# Power_management.net
KiCad netlist of a schematic drawn in Altium Designer
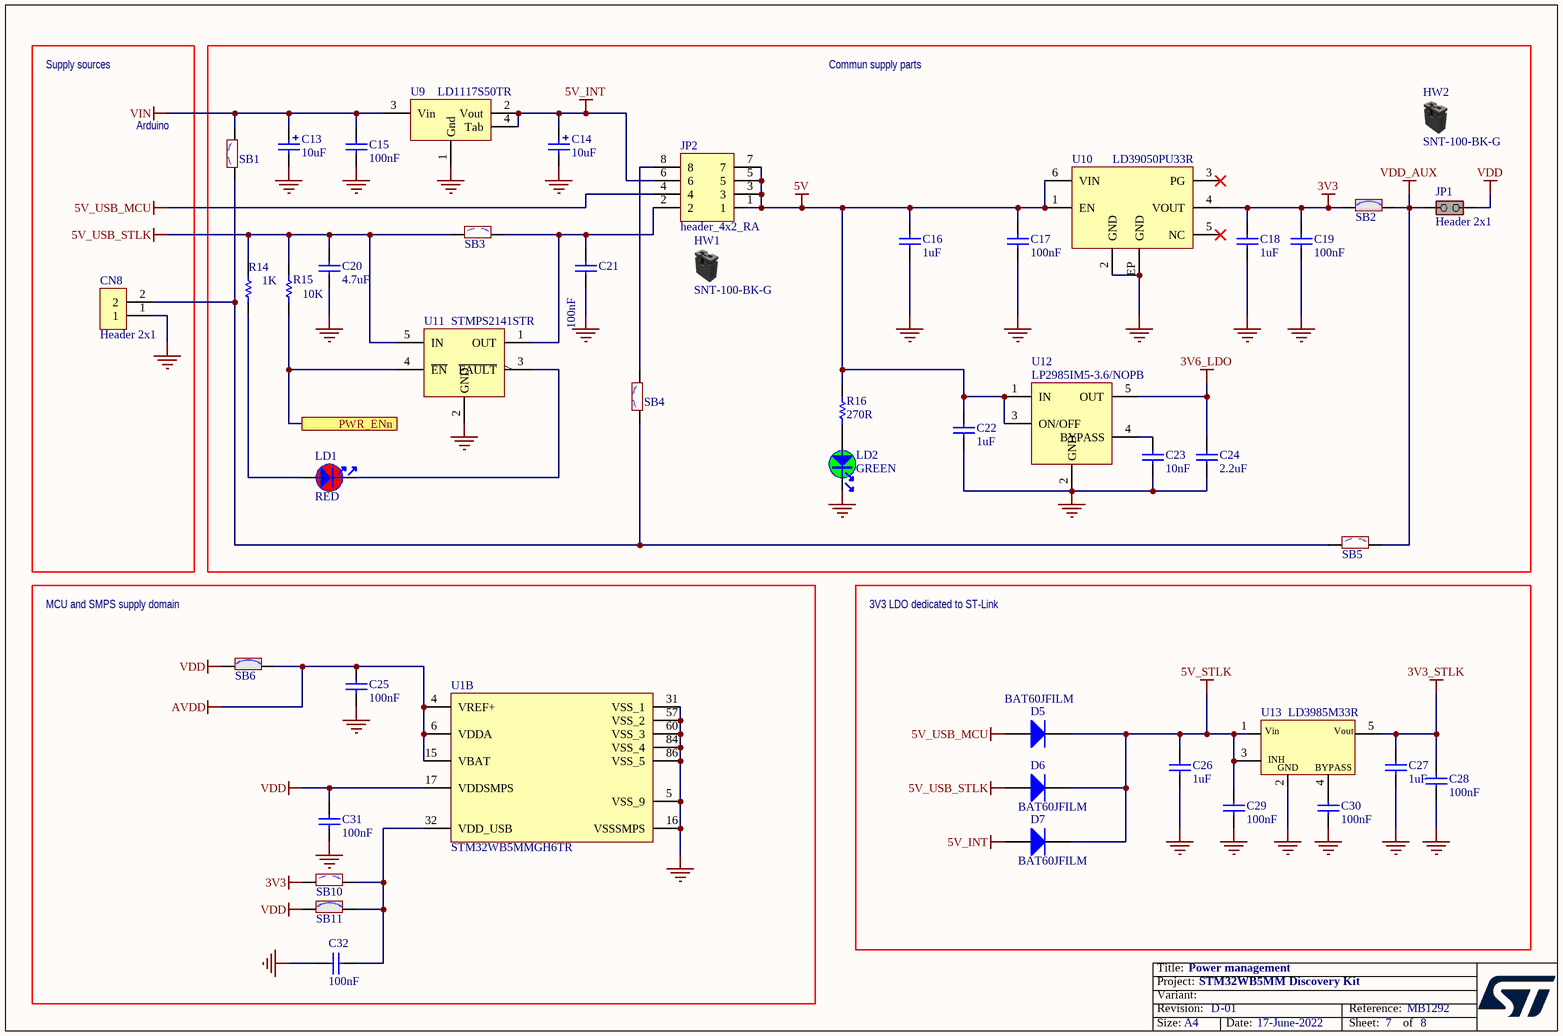
[diagram p0: Power_management.SchDoc]

(export (version "E")
  (design (tool "Eeschema 10.0.6"))
  (components
    (comp (ref "C13")
      (value "10uF")
      (footprint "CPOL_TAJ-B_1210_H210")
      (description "Capacitor, Tantalum, 10uF, 25V,2.5ohms, 10%, pkg Type_B (3528 metric), T=1.9mm")
      (fields
        (field (name "INTERNAL_PART_NUMBER") "MCD-00324")
        (field (name "MANUFACTURER_PART_NUMBER") "TAJB106K025RNJ")
      )
      (libsource (lib "MCD_PARTS_database") (part "Cap_POL_TANA"))
    )
    (comp (ref "C14")
      (value "10uF")
      (footprint "CPOL_TAJ-B_1210_H210")
      (description "Capacitor, Tantalum, 10uF, 25V,2.5ohms, 10%, pkg Type_B (3528 metric), T=1.9mm")
      (fields
        (field (name "INTERNAL_PART_NUMBER") "MCD-00324")
        (field (name "MANUFACTURER_PART_NUMBER") "TAJB106K025RNJ")
      )
      (libsource (lib "MCD_PARTS_database") (part "Cap_POL_TANA"))
    )
    (comp (ref "C15")
      (value "100nF")
      (footprint "C0805_H0P85")
      (description "Capacitor, MLCC, 100nF, 50V, X7R, 10%, 0805, T=0,85mm")
      (fields
        (field (name "INTERNAL_PART_NUMBER") "MCD-01525")
        (field (name "MANUFACTURER_PART_NUMBER") "CC0805KRX7R9BB104")
      )
      (libsource (lib "MCD_PARTS_database") (part "Capacitor"))
    )
    (comp (ref "C16")
      (value "1uF")
      (footprint "C0805_H0P85")
      (description "Capacitor, MLCC, 1uF, 16V, X5R, +/-10%, 0805, T=0.85mm")
      (fields
        (field (name "INTERNAL_PART_NUMBER") "MCD-01550")
        (field (name "MANUFACTURER_PART_NUMBER") "CC0805KRX5R7BB105")
      )
      (libsource (lib "MCD_PARTS_database") (part "Capacitor"))
    )
    (comp (ref "C17")
      (value "100nF")
      (footprint "C0201_H0P3")
      (description "Capacitor, MLCC,100nF, 10V, X7R, +/-10%, 0201, T=0.3mm")
      (fields
        (field (name "INTERNAL_PART_NUMBER") "MCD-01535")
        (field (name "MANUFACTURER_PART_NUMBER") "GRM033R61A104KE15")
      )
      (libsource (lib "MCD_PARTS_database") (part "Capacitor"))
    )
    (comp (ref "C18")
      (value "1uF")
      (footprint "C0805_H0P85")
      (description "Capacitor, MLCC, 1uF, 16V, X5R, +/-10%, 0805, T=0.85mm")
      (fields
        (field (name "INTERNAL_PART_NUMBER") "MCD-01550")
        (field (name "MANUFACTURER_PART_NUMBER") "CC0805KRX5R7BB105")
      )
      (libsource (lib "MCD_PARTS_database") (part "Capacitor"))
    )
    (comp (ref "C19")
      (value "100nF")
      (footprint "C0201_H0P3")
      (description "Capacitor, MLCC,100nF, 10V, X7R, +/-10%, 0201, T=0.3mm")
      (fields
        (field (name "INTERNAL_PART_NUMBER") "MCD-01535")
        (field (name "MANUFACTURER_PART_NUMBER") "GRM033R61A104KE15")
      )
      (libsource (lib "MCD_PARTS_database") (part "Capacitor"))
    )
    (comp (ref "C20")
      (value "4.7uF")
      (footprint "C0603_H0P8")
      (description "Capacitor, MLCC, 4.7uF, 10V, X5R, +/-10%, 0603, T=0.8mm")
      (fields
        (field (name "INTERNAL_PART_NUMBER") "MCD-01721")
        (field (name "MANUFACTURER_PART_NUMBER") "CC0603KRX5R6BB475")
      )
      (libsource (lib "MCD_PARTS_database") (part "Capacitor"))
    )
    (comp (ref "C21")
      (value "100nF")
      (footprint "C0805_H0P85")
      (description "Capacitor, MLCC, 100nF, 50V, X7R, 10%, 0805, T=0,85mm")
      (fields
        (field (name "INTERNAL_PART_NUMBER") "MCD-01525")
        (field (name "MANUFACTURER_PART_NUMBER") "CC0805KRX7R9BB104")
      )
      (libsource (lib "MCD_PARTS_database") (part "Capacitor"))
    )
    (comp (ref "C22")
      (value "1uF")
      (footprint "C0603")
      (description "Capacitor, MLCC, 1uF, 16V, X5R, +/-10%, 0603, T=0,8mm")
      (fields
        (field (name "INTERNAL_PART_NUMBER") "MCD-00010")
        (field (name "MANUFACTURER_PART_NUMBER") "CC0603KRX5R7BB105")
      )
      (libsource (lib "MCD_PARTS_database") (part "Capacitor"))
    )
    (comp (ref "C23")
      (value "10nF")
      (footprint "C0603")
      (description "Capacitor, MLCC, 10nF, 16V, X7R, +/-10%, 0603, T=0.8mm")
      (fields
        (field (name "INTERNAL_PART_NUMBER") "MCD-01007")
        (field (name "MANUFACTURER_PART_NUMBER") "CC0603KRX7R7BB103")
      )
      (libsource (lib "MCD_PARTS_database") (part "Capacitor"))
    )
    (comp (ref "C24")
      (value "2.2uF")
      (footprint "C0603")
      (description "Capacitor, MLCC, 2.2uF, 10V, X5R, +/- 10%, 0603, T=0,8mm")
      (fields
        (field (name "INTERNAL_PART_NUMBER") "MCD-00012")
        (field (name "MANUFACTURER_PART_NUMBER") "CC0603KRX5R6BB225")
      )
      (libsource (lib "MCD_PARTS_database") (part "Capacitor"))
    )
    (comp (ref "C25")
      (value "100nF")
      (footprint "C0201_H0P3")
      (description "Capacitor, MLCC,100nF, 10V, X7R, +/-10%, 0201, T=0.3mm")
      (fields
        (field (name "INTERNAL_PART_NUMBER") "MCD-01535")
        (field (name "MANUFACTURER_PART_NUMBER") "GRM033R61A104KE15")
      )
      (libsource (lib "MCD_PARTS_database") (part "Capacitor"))
    )
    (comp (ref "C26")
      (value "1uF")
      (footprint "C0402")
      (description "Capacitor, MLCC, 1uF, 10V, X5R, +/-10%, 0402, T=0.5mm")
      (fields
        (field (name "INTERNAL_PART_NUMBER") "MCD-01722")
        (field (name "MANUFACTURER_PART_NUMBER") "CC0402KRX5R6BB105")
      )
      (libsource (lib "MCD_PARTS_database") (part "Capacitor"))
    )
    (comp (ref "C27")
      (value "1uF")
      (footprint "C0402")
      (description "Capacitor, MLCC, 1uF, 10V, X5R, +/-10%, 0402, T=0.5mm")
      (fields
        (field (name "INTERNAL_PART_NUMBER") "MCD-01722")
        (field (name "MANUFACTURER_PART_NUMBER") "CC0402KRX5R6BB105")
      )
      (libsource (lib "MCD_PARTS_database") (part "Capacitor"))
    )
    (comp (ref "C28")
      (value "100nF")
      (footprint "C0201_H0P3")
      (description "Capacitor, MLCC,100nF, 10V, X7R, +/-10%, 0201, T=0.3mm")
      (fields
        (field (name "INTERNAL_PART_NUMBER") "MCD-01535")
        (field (name "MANUFACTURER_PART_NUMBER") "GRM033R61A104KE15")
      )
      (libsource (lib "MCD_PARTS_database") (part "Capacitor"))
    )
    (comp (ref "C29")
      (value "100nF")
      (footprint "C0201_H0P3")
      (description "Capacitor, MLCC,100nF, 10V, X7R, +/-10%, 0201, T=0.3mm")
      (fields
        (field (name "INTERNAL_PART_NUMBER") "MCD-01535")
        (field (name "MANUFACTURER_PART_NUMBER") "GRM033R61A104KE15")
      )
      (libsource (lib "MCD_PARTS_database") (part "Capacitor"))
    )
    (comp (ref "C30")
      (value "100nF")
      (footprint "C0201_H0P3")
      (description "Capacitor, MLCC,100nF, 10V, X7R, +/-10%, 0201, T=0.3mm")
      (fields
        (field (name "INTERNAL_PART_NUMBER") "MCD-01535")
        (field (name "MANUFACTURER_PART_NUMBER") "GRM033R61A104KE15")
      )
      (libsource (lib "MCD_PARTS_database") (part "Capacitor"))
    )
    (comp (ref "C31")
      (value "100nF")
      (footprint "C0201_H0P3")
      (description "Capacitor, MLCC,100nF, 10V, X7R, +/-10%, 0201, T=0.3mm")
      (fields
        (field (name "INTERNAL_PART_NUMBER") "MCD-01535")
        (field (name "MANUFACTURER_PART_NUMBER") "GRM033R61A104KE15")
      )
      (libsource (lib "MCD_PARTS_database") (part "Capacitor"))
    )
    (comp (ref "C32")
      (value "100nF")
      (footprint "C0201_H0P3")
      (description "Capacitor, MLCC,100nF, 10V, X7R, +/-10%, 0201, T=0.3mm")
      (fields
        (field (name "INTERNAL_PART_NUMBER") "MCD-01535")
        (field (name "MANUFACTURER_PART_NUMBER") "GRM033R61A104KE15")
      )
      (libsource (lib "MCD_PARTS_database") (part "Capacitor"))
    )
    (comp (ref "CN8")
      (value "Header 2x1")
      (footprint "CON_LYCONN_313102S141346")
      (description "Header 2x1, 2.54mm, VR, TH, height 5.84mm/5.08 mm, height total 13.46 mm")
      (fields
        (field (name "INTERNAL_PART_NUMBER") "MCD-01668")
        (field (name "MANUFACTURER_PART_NUMBER") "313102S141346")
      )
      (libsource (lib "MCD_PARTS_database") (part "Header 2x1"))
    )
    (comp (ref "D5")
      (value "BAT60JFILM")
      (footprint "DIO_SOD323")
      (fields
        (field (name "INTERNAL_PART_NUMBER") "MCD-00034")
        (field (name "MANUFACTURER") "STMICROELECTRONICS")
        (field (name "BMS_PART_NUMBER") "9151097")
      )
      (libsource (lib "MCD_PARTS_database") (part "BAT60JFILM"))
    )
    (comp (ref "D6")
      (value "BAT60JFILM")
      (footprint "DIO_SOD323")
      (fields
        (field (name "INTERNAL_PART_NUMBER") "MCD-00034")
        (field (name "MANUFACTURER") "STMICROELECTRONICS")
        (field (name "BMS_PART_NUMBER") "9151097")
      )
      (libsource (lib "MCD_PARTS_database") (part "BAT60JFILM"))
    )
    (comp (ref "D7")
      (value "BAT60JFILM")
      (footprint "DIO_SOD323")
      (fields
        (field (name "INTERNAL_PART_NUMBER") "MCD-00034")
        (field (name "MANUFACTURER") "STMICROELECTRONICS")
        (field (name "BMS_PART_NUMBER") "9151097")
      )
      (libsource (lib "MCD_PARTS_database") (part "BAT60JFILM"))
    )
    (comp (ref "HW1")
      (value "SNT-100-BK-G")
      (description "SHUNT 2.54mm BLACK")
      (fields (field (name "INTERNAL_PART_NUMBER") "MCD-00043") (field (name "MANUFACTURER") "SAMTEC"))
      (libsource (lib "MCD_PARTS_database") (part "Shunt Black 2.54mm"))
    )
    (comp (ref "HW2")
      (value "SNT-100-BK-G")
      (description "SHUNT 2.54mm BLACK")
      (fields (field (name "INTERNAL_PART_NUMBER") "MCD-00043") (field (name "MANUFACTURER") "SAMTEC"))
      (libsource (lib "MCD_PARTS_database") (part "Shunt Black 2.54mm"))
    )
    (comp (ref "JP1")
      (value "Header 2x1")
      (footprint "CON_SAMTEC_TSW-102-07-G-S")
      (description "Header, 2x1, 2,54mm, VR, TH, Height 5.84mm/2.54mm - Shunt Fitted by default")
      (fields
        (field (name "INTERNAL_PART_NUMBER") "MCD-01904")
        (field (name "MANUFACTURER_PART_NUMBER") "TSW-102-07-G-S")
      )
      (libsource (lib "MCD_PARTS_database") (part "Jumper_Header 2x1 Fitted"))
    )
    (comp (ref "JP2")
      (value "header_4x2_RA")
      (footprint "CON_SAMTEC_TSW-104-08-F-D-RA")
      (description "Header, 4x2, 2,29mm, RA, TH, height 5,84mm")
      (fields
        (field (name "INTERNAL_PART_NUMBER") "MCD-02037")
        (field (name "MANUFACTURER_PART_NUMBER") "TSW-104-08-F-D-RA")
      )
      (libsource (lib "MCD_PARTS_database") (part "Header 4x2"))
    )
    (comp (ref "LD1")
      (value "RED")
      (footprint "LED_0603_VISHAY_VLMS1300-GS08_RED_1A2K_H0P8")
      (description "LED Red, 0603 SMD, 2V Forward Voltage")
      (fields (field (name "INTERNAL_PART_NUMBER") "MCD-00587") (field (name "MANUFACTURER") "VISHAY"))
      (libsource (lib "MCD_PARTS_database") (part "LED_red"))
    )
    (comp (ref "LD2")
      (value "GREEN")
      (footprint "LED_0603_OSRAM_LG-Q396-PS-35_GREEN_1A2K_H0P4")
      (description "LED Green, 0603 SMD, Forward Voltage Typ=2V, Max=2.5V")
      (fields
        (field (name "INTERNAL_PART_NUMBER") "MCD-00588")
        (field (name "MANUFACTURER_PART_NUMBER") "LG Q396-PS-35")
      )
      (libsource (lib "MCD_PARTS_database") (part "LED_green"))
    )
    (comp (ref "R14")
      (value "1K")
      (footprint "R0603")
      (description "Resistor,1K,0603,1%,1/10W")
      (fields
        (field (name "INTERNAL_PART_NUMBER") "MCD-00070")
        (field (name "MANUFACTURER_PART_NUMBER") "RC0603FR-071KL")
      )
      (libsource (lib "MCD_PARTS_database") (part "Resistor"))
    )
    (comp (ref "R15")
      (value "10K")
      (footprint "R0603")
      (description "Resistor,10K,0603,1%,1/10W")
      (fields
        (field (name "INTERNAL_PART_NUMBER") "MCD-00220")
        (field (name "MANUFACTURER_PART_NUMBER") "RC0603FR-0710KL")
      )
      (libsource (lib "MCD_PARTS_database") (part "Resistor"))
    )
    (comp (ref "R16")
      (value "270R")
      (footprint "R0603")
      (description "Resistor,270R,0603,1%,1/10W")
      (fields
        (field (name "INTERNAL_PART_NUMBER") "MCD-00442")
        (field (name "MANUFACTURER_PART_NUMBER") "RC0603FR-07270RL")
      )
      (libsource (lib "MCD_PARTS_database") (part "Resistor"))
    )
    (comp (ref "SB1")
      (value "SB_OFF")
      (footprint "SOLDER-BRIDGE_R0603-0R")
      (description "Solder Bridge OFF")
      (fields
        (field (name "INTERNAL_PART_NUMBER") "MCD-00072")
        (field (name "MANUFACTURER_PART_NUMBER") "RC0603JR-070RL")
      )
      (libsource (lib "") (part "SB_OFF_1"))
    )
    (comp (ref "SB2")
      (value "SB_ON")
      (footprint "SOLDER-BRIDGE_R0603-0R")
      (description "Solder Bridge ON")
      (fields
        (field (name "INTERNAL_PART_NUMBER") "MCD-00071")
        (field (name "MANUFACTURER_PART_NUMBER") "RC0603JR-070RL")
      )
      (libsource (lib "MCD_PARTS_database") (part "SB_ON"))
    )
    (comp (ref "SB3")
      (value "SB_OFF")
      (footprint "SOLDER-BRIDGE_R0603-0R")
      (description "Solder Bridge OFF")
      (fields
        (field (name "INTERNAL_PART_NUMBER") "MCD-00072")
        (field (name "MANUFACTURER_PART_NUMBER") "RC0603JR-070RL")
      )
      (libsource (lib "MCD_PARTS_database") (part "SB_OFF"))
    )
    (comp (ref "SB4")
      (value "SB_OFF")
      (footprint "SOLDER-BRIDGE_R0603-0R")
      (description "Solder Bridge OFF")
      (fields
        (field (name "INTERNAL_PART_NUMBER") "MCD-00072")
        (field (name "MANUFACTURER_PART_NUMBER") "RC0603JR-070RL")
      )
      (libsource (lib "") (part "SB_OFF_1"))
    )
    (comp (ref "SB5")
      (value "SB_OFF")
      (footprint "SOLDER-BRIDGE_R0603-0R")
      (description "Solder Bridge OFF")
      (fields
        (field (name "INTERNAL_PART_NUMBER") "MCD-00072")
        (field (name "MANUFACTURER_PART_NUMBER") "RC0603JR-070RL")
      )
      (libsource (lib "MCD_PARTS_database") (part "SB_OFF"))
    )
    (comp (ref "SB6")
      (value "SB_ON")
      (footprint "SOLDER-BRIDGE_R0603-0R")
      (description "Solder Bridge ON")
      (fields
        (field (name "INTERNAL_PART_NUMBER") "MCD-00071")
        (field (name "MANUFACTURER_PART_NUMBER") "RC0603JR-070RL")
      )
      (libsource (lib "MCD_PARTS_database") (part "SB_ON"))
    )
    (comp (ref "SB10")
      (value "SB_OFF")
      (footprint "SOLDER-BRIDGE_R0603-0R")
      (description "Solder Bridge OFF")
      (fields
        (field (name "INTERNAL_PART_NUMBER") "MCD-00072")
        (field (name "MANUFACTURER_PART_NUMBER") "RC0603JR-070RL")
      )
      (libsource (lib "MCD_PARTS_database") (part "SB_OFF"))
    )
    (comp (ref "SB11")
      (value "SB_ON")
      (footprint "SOLDER-BRIDGE_R0603-0R")
      (description "Solder Bridge ON")
      (fields
        (field (name "INTERNAL_PART_NUMBER") "MCD-00071")
        (field (name "MANUFACTURER_PART_NUMBER") "RC0603JR-070RL")
      )
      (libsource (lib "MCD_PARTS_database") (part "SB_ON"))
    )
    (comp (ref "U1")
      (value "STM32WB5MMGH6TR")
      (footprint "MOD_DORY_STM_86P_7P3X11_H1P342")
      (description "STM32 BLE module based on STM32WB55")
      (fields
        (field (name "INTERNAL_PART_NUMBER") "MCD-01965")
        (field (name "MANUFACTURER") "STMICROELECTRONICS")
      )
      (libsource (lib "MCD_PARTS_database") (part "STM32WB5MMGH6TR"))
    )
    (comp (ref "U9")
      (value "LD1117S50TR")
      (footprint "REG_SOT223-TAB")
      (description "IC REG LDO 5V 0.8A SOT223")
      (fields
        (field (name "INTERNAL_PART_NUMBER") "MCD-00088")
        (field (name "MANUFACTURER") "STMICROELECTRONICS")
      )
      (libsource (lib "MCD_PARTS_database") (part "LD1117S50TR"))
    )
    (comp (ref "U10")
      (value "LD39050PU33R")
      (footprint "ICC_DFN6-EPAD_3X3_P095")
      (description "Low quiescent current and low noise voltage regulators")
      (fields
        (field (name "INTERNAL_PART_NUMBER") "MCD-00215")
        (field (name "MANUFACTURER") "STMICROELECTRONICS")
      )
      (libsource (lib "MCD_PARTS_database") (part "LD39050PU33R"))
    )
    (comp (ref "U11")
      (value "STMPS2141STR")
      (footprint "MOS_SOT23-5L")
      (description "Enhanced single channel power switches with active low enable pin")
      (fields
        (field (name "INTERNAL_PART_NUMBER") "MCD-00083")
        (field (name "MANUFACTURER") "STMICROELECTRONICS")
      )
      (libsource (lib "MCD_PARTS_database") (part "STMPS2141STR"))
    )
    (comp (ref "U12")
      (value "LP2985IM5-3.6/NOPB")
      (footprint "REG_SOT23-5L")
      (description "LDO VOLTAGE REGULATOR, 3.6V, 150mA, 5-SOT-23, FULL REEL")
      (fields
        (field (name "INTERNAL_PART_NUMBER") "MCD-01030")
        (field (name "MANUFACTURER") "TEXAS INSTRUMENTS")
      )
      (libsource (lib "MCD_PARTS_database") (part "LP2985IM5-3.6/NOPB"))
    )
    (comp (ref "U13")
      (value "LD3985M33R")
      (footprint "REG_SOT23-5L")
      (description "Ultra low drop-low noise BiCMOS voltage, regulators low ESR capacitors compatible")
      (fields
        (field (name "INTERNAL_PART_NUMBER") "MCD-00086")
        (field (name "MANUFACTURER") "STMICROELECTRONICS")
      )
      (libsource (lib "MCD_PARTS_database") (part "LD3985M33R"))
    )
  )
  (nets
    (net (code "1") (name "/PWR_ENn") (class "Default")
      (node (ref "R15") (pin "1") (pinfunction "1_1") (pintype "passive"))
      (node (ref "U11") (pin "4") (pinfunction "~{EN}_4") (pintype "passive"))
    )
    (net (code "2") (name "3V3") (class "Default")
      (node (ref "C18") (pin "2") (pinfunction "2_2") (pintype "passive"))
      (node (ref "C19") (pin "2") (pinfunction "2_2") (pintype "passive"))
      (node (ref "SB10") (pin "1") (pinfunction "1_1") (pintype "passive"))
      (node (ref "SB2") (pin "1") (pinfunction "1_1") (pintype "passive"))
      (node (ref "U10") (pin "4") (pinfunction "VOUT_4") (pintype "passive"))
    )
    (net (code "3") (name "3V3_STLK") (class "Default")
      (node (ref "C27") (pin "2") (pinfunction "2_2") (pintype "passive"))
      (node (ref "C28") (pin "2") (pinfunction "2_2") (pintype "passive"))
      (node (ref "U13") (pin "5") (pinfunction "Vout_5") (pintype "passive"))
    )
    (net (code "4") (name "3V6_LDO") (class "Default")
      (node (ref "C24") (pin "2") (pinfunction "2_2") (pintype "passive"))
      (node (ref "U12") (pin "5") (pinfunction "OUT_5") (pintype "passive"))
    )
    (net (code "5") (name "5V") (class "Default")
      (node (ref "C16") (pin "2") (pinfunction "2_2") (pintype "passive"))
      (node (ref "C17") (pin "2") (pinfunction "2_2") (pintype "passive"))
      (node (ref "C22") (pin "1") (pinfunction "1_1") (pintype "passive"))
      (node (ref "JP2") (pin "1") (pinfunction "1_1") (pintype "passive"))
      (node (ref "JP2") (pin "3") (pinfunction "3_3") (pintype "passive"))
      (node (ref "JP2") (pin "5") (pinfunction "5_5") (pintype "passive"))
      (node (ref "JP2") (pin "7") (pinfunction "7_7") (pintype "passive"))
      (node (ref "R16") (pin "2") (pinfunction "2_2") (pintype "passive"))
      (node (ref "U10") (pin "1") (pinfunction "EN_1") (pintype "passive"))
      (node (ref "U10") (pin "6") (pinfunction "VIN_6") (pintype "passive"))
      (node (ref "U12") (pin "1") (pinfunction "IN_1") (pintype "passive"))
      (node (ref "U12") (pin "3") (pinfunction "ON/OFF_3") (pintype "passive"))
    )
    (net (code "6") (name "5V_INT") (class "Default")
      (node (ref "C14") (pin "1") (pinfunction "1_1") (pintype "passive"))
      (node (ref "D7") (pin "1") (pinfunction "A_1") (pintype "passive"))
      (node (ref "JP2") (pin "6") (pinfunction "6_6") (pintype "passive"))
      (node (ref "U9") (pin "2") (pinfunction "Vout_2") (pintype "passive"))
      (node (ref "U9") (pin "4") (pinfunction "Tab_4") (pintype "passive"))
    )
    (net (code "7") (name "5V_STLK") (class "Default")
      (node (ref "C26") (pin "2") (pinfunction "2_2") (pintype "passive"))
      (node (ref "C29") (pin "2") (pinfunction "2_2") (pintype "passive"))
      (node (ref "D5") (pin "2") (pinfunction "K_2") (pintype "passive"))
      (node (ref "D6") (pin "2") (pinfunction "K_2") (pintype "passive"))
      (node (ref "D7") (pin "2") (pinfunction "K_2") (pintype "passive"))
      (node (ref "U13") (pin "1") (pinfunction "Vin_1") (pintype "passive"))
      (node (ref "U13") (pin "3") (pinfunction "CE_3") (pintype "passive"))
    )
    (net (code "8") (name "5V_USB_MCU") (class "Default")
      (node (ref "D5") (pin "1") (pinfunction "A_1") (pintype "passive"))
      (node (ref "JP2") (pin "4") (pinfunction "4_4") (pintype "passive"))
    )
    (net (code "9") (name "5V_USB_STLK") (class "Default")
      (node (ref "C20") (pin "2") (pinfunction "2_2") (pintype "passive"))
      (node (ref "D6") (pin "1") (pinfunction "A_1") (pintype "passive"))
      (node (ref "R14") (pin "2") (pinfunction "2_2") (pintype "passive"))
      (node (ref "R15") (pin "2") (pinfunction "2_2") (pintype "passive"))
      (node (ref "SB3") (pin "1") (pinfunction "1_1") (pintype "passive"))
      (node (ref "U11") (pin "5") (pinfunction "IN_5") (pintype "passive"))
    )
    (net (code "10") (name "AVDD") (class "Default")
      (node (ref "C25") (pin "2") (pinfunction "2_2") (pintype "passive"))
      (node (ref "SB6") (pin "2") (pinfunction "2_2") (pintype "passive"))
      (node (ref "U1") (pin "15") (pinfunction "VBAT_15") (pintype "passive"))
      (node (ref "U1") (pin "4") (pinfunction "VREF+_4") (pintype "passive"))
      (node (ref "U1") (pin "6") (pinfunction "VDDA_6") (pintype "passive"))
    )
    (net (code "11") (name "GND") (class "Default")
      (node (ref "C13") (pin "2") (pinfunction "2_2") (pintype "passive"))
      (node (ref "C14") (pin "2") (pinfunction "2_2") (pintype "passive"))
      (node (ref "C15") (pin "1") (pinfunction "1_1") (pintype "passive"))
      (node (ref "C16") (pin "1") (pinfunction "1_1") (pintype "passive"))
      (node (ref "C17") (pin "1") (pinfunction "1_1") (pintype "passive"))
      (node (ref "C18") (pin "1") (pinfunction "1_1") (pintype "passive"))
      (node (ref "C19") (pin "1") (pinfunction "1_1") (pintype "passive"))
      (node (ref "C20") (pin "1") (pinfunction "1_1") (pintype "passive"))
      (node (ref "C21") (pin "1") (pinfunction "1_1") (pintype "passive"))
      (node (ref "C22") (pin "2") (pinfunction "2_2") (pintype "passive"))
      (node (ref "C23") (pin "1") (pinfunction "1_1") (pintype "passive"))
      (node (ref "C24") (pin "1") (pinfunction "1_1") (pintype "passive"))
      (node (ref "C25") (pin "1") (pinfunction "1_1") (pintype "passive"))
      (node (ref "C26") (pin "1") (pinfunction "1_1") (pintype "passive"))
      (node (ref "C27") (pin "1") (pinfunction "1_1") (pintype "passive"))
      (node (ref "C28") (pin "1") (pinfunction "1_1") (pintype "passive"))
      (node (ref "C29") (pin "1") (pinfunction "1_1") (pintype "passive"))
      (node (ref "C30") (pin "1") (pinfunction "1_1") (pintype "passive"))
      (node (ref "C31") (pin "1") (pinfunction "1_1") (pintype "passive"))
      (node (ref "C32") (pin "2") (pinfunction "2_2") (pintype "passive"))
      (node (ref "CN8") (pin "1") (pinfunction "1_1") (pintype "passive"))
      (node (ref "LD2") (pin "2") (pintype "passive"))
      (node (ref "U1") (pin "16") (pinfunction "VSSSMPS_16") (pintype "passive"))
      (node (ref "U1") (pin "31") (pinfunction "VSS_1_31") (pintype "passive"))
      (node (ref "U1") (pin "5") (pinfunction "VSS_9_5") (pintype "passive"))
      (node (ref "U1") (pin "57") (pinfunction "VSS_2_57") (pintype "passive"))
      (node (ref "U1") (pin "60") (pinfunction "VSS_3_60") (pintype "passive"))
      (node (ref "U1") (pin "84") (pinfunction "VSS_4_84") (pintype "passive"))
      (node (ref "U1") (pin "86") (pinfunction "VSS_5_86") (pintype "passive"))
      (node (ref "U10") (pin "2") (pinfunction "GND_2") (pintype "passive"))
      (node (ref "U10") (pin "EP") (pinfunction "GND_EP") (pintype "passive"))
      (node (ref "U11") (pin "2") (pinfunction "GND_2") (pintype "passive"))
      (node (ref "U12") (pin "2") (pinfunction "GND_2") (pintype "passive"))
      (node (ref "U13") (pin "2") (pinfunction "GND_2") (pintype "passive"))
      (node (ref "U9") (pin "1") (pinfunction "Gnd_1") (pintype "passive"))
    )
    (net (code "12") (name "Net-(CN8-Pad2)") (class "Default")
      (node (ref "CN8") (pin "2") (pinfunction "2_2") (pintype "passive"))
      (node (ref "SB1") (pin "1") (pinfunction "1_1") (pintype "passive"))
      (node (ref "SB4") (pin "1") (pinfunction "1_1") (pintype "passive"))
      (node (ref "SB5") (pin "1") (pinfunction "1_1") (pintype "passive"))
    )
    (net (code "13") (name "Net-(JP2-Pad8)") (class "Default")
      (node (ref "JP2") (pin "8") (pinfunction "8_8") (pintype "passive"))
      (node (ref "SB4") (pin "2") (pinfunction "2_2") (pintype "passive"))
    )
    (net (code "14") (name "Net-(LD1-Pad1)") (class "Default")
      (node (ref "LD1") (pin "1") (pintype "passive"))
      (node (ref "R14") (pin "1") (pinfunction "1_1") (pintype "passive"))
    )
    (net (code "15") (name "Net-(LD2-Pad1)") (class "Default")
      (node (ref "LD2") (pin "1") (pintype "passive"))
      (node (ref "R16") (pin "1") (pinfunction "1_1") (pintype "passive"))
    )
    (net (code "16") (name "Net-(U1B-VDD_USB)") (class "Default")
      (node (ref "C32") (pin "1") (pinfunction "1_1") (pintype "passive"))
      (node (ref "SB10") (pin "2") (pinfunction "2_2") (pintype "passive"))
      (node (ref "SB11") (pin "2") (pinfunction "2_2") (pintype "passive"))
      (node (ref "U1") (pin "32") (pinfunction "VDD_USB_32") (pintype "passive"))
    )
    (net (code "17") (name "Net-(U11-OUT)") (class "Default")
      (node (ref "C21") (pin "2") (pinfunction "2_2") (pintype "passive"))
      (node (ref "JP2") (pin "2") (pinfunction "2_2") (pintype "passive"))
      (node (ref "SB3") (pin "2") (pinfunction "2_2") (pintype "passive"))
      (node (ref "U11") (pin "1") (pinfunction "OUT_1") (pintype "passive"))
    )
    (net (code "18") (name "Net-(U11-~{FAULT})") (class "Default")
      (node (ref "LD1") (pin "2") (pintype "passive"))
      (node (ref "U11") (pin "3") (pinfunction "~{FAULT}_3") (pintype "passive"))
    )
    (net (code "19") (name "Net-(U12-BYPASS)") (class "Default")
      (node (ref "C23") (pin "2") (pinfunction "2_2") (pintype "passive"))
      (node (ref "U12") (pin "4") (pinfunction "BYPASS_4") (pintype "passive"))
    )
    (net (code "20") (name "Net-(U13-BYPASS)") (class "Default")
      (node (ref "C30") (pin "2") (pinfunction "2_2") (pintype "passive"))
      (node (ref "U13") (pin "4") (pinfunction "BYPASS_4") (pintype "passive"))
    )
    (net (code "21") (name "VDD") (class "Default")
      (node (ref "C31") (pin "2") (pinfunction "2_2") (pintype "passive"))
      (node (ref "JP1") (pin "2") (pinfunction "NO_2") (pintype "passive"))
      (node (ref "SB11") (pin "1") (pinfunction "1_1") (pintype "passive"))
      (node (ref "SB6") (pin "1") (pinfunction "1_1") (pintype "passive"))
      (node (ref "U1") (pin "17") (pinfunction "VDDSMPS_17") (pintype "passive"))
    )
    (net (code "22") (name "VDD_AUX") (class "Default")
      (node (ref "JP1") (pin "1") (pinfunction "COMMON_1") (pintype "passive"))
      (node (ref "SB2") (pin "2") (pinfunction "2_2") (pintype "passive"))
      (node (ref "SB5") (pin "2") (pinfunction "2_2") (pintype "passive"))
    )
    (net (code "23") (name "VIN") (class "Default")
      (node (ref "C13") (pin "1") (pinfunction "1_1") (pintype "passive"))
      (node (ref "C15") (pin "2") (pinfunction "2_2") (pintype "passive"))
      (node (ref "SB1") (pin "2") (pinfunction "2_2") (pintype "passive"))
      (node (ref "U9") (pin "3") (pinfunction "Vin_3") (pintype "passive"))
    )
    (net (code "24") (name "unconnected-(U10-NC-Pad5)") (class "Default")
      (node (ref "U10") (pin "5") (pinfunction "NC_5") (pintype "passive+no_connect"))
    )
    (net (code "25") (name "unconnected-(U10-PG-Pad3)") (class "Default")
      (node (ref "U10") (pin "3") (pinfunction "PG_3") (pintype "passive+no_connect"))
    )
  )
)
